# v2_0.net
KiCad netlist of a schematic drawn in Altium Designer
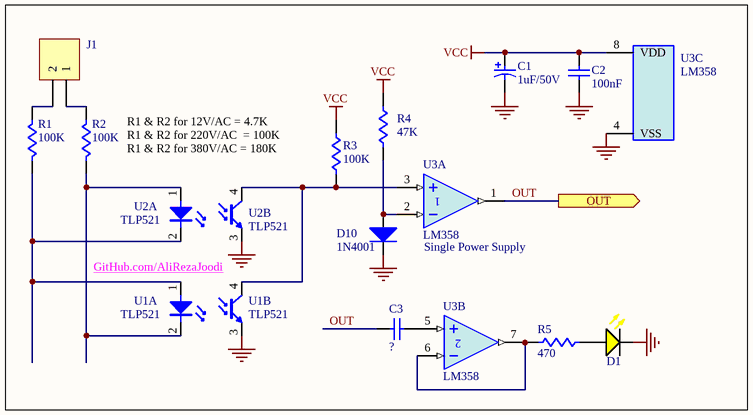
[diagram p0: v2.0.SchDoc]

(export (version "E")
  (design (tool "Eeschema 10.0.6"))
  (components
    (comp (ref "C1")
      (value "1uF/50V")
      (footprint "C_THD_EL_(P2.54-D6-H11)")
      (description "Capacitor, Electrolytic")
      (libsource (lib "Passive") (part "Capacitor_Electrolytic"))
    )
    (comp (ref "C2")
      (value "100nF")
      (footprint "C_THD_CER_(P2.54-D3.5-T1.5)")
      (description "Capacitor, Ceramic Multilayer")
      (libsource (lib "Passive") (part "Capacitor_Ceramic"))
    )
    (comp (ref "C3")
      (value "?")
      (footprint "C_THD_CER_(P2.54-D3.5-T1.5)")
      (description "Capacitor, Ceramic Multilayer")
      (libsource (lib "Passive") (part "Capacitor_Ceramic"))
    )
    (comp (ref "D1")
      (value "YELLOW")
      (footprint "LED_THD_5MM_YELLOW")
      (description "LED, Yellow")
      (fields (field (name "MANUFACTURER") "Generic Components") (field (name "PUBLISHER") "Altium Limited"))
      (libsource (lib "Display") (part "LED_YELLOW"))
    )
    (comp (ref "D10")
      (value "1N4001")
      (footprint "DIODE-0.4")
      (description "Default Diode")
      (fields (field (name "MANUFACTURER") "Generic Components") (field (name "PUBLISHER") "Altium Limited"))
      (libsource (lib "Miscellaneous Devices") (part "Diode"))
    )
    (comp (ref "J1")
      (value "Header 2")
      (footprint "Fonics_2PIN_1")
      (description "Header, 2-Pin")
      (fields (field (name "PUBLISHER") "Altium Limited"))
      (libsource (lib "Miscellaneous Connectors") (part "Header 2"))
    )
    (comp (ref "R1")
      (value "100K")
      (footprint "AXIAL-0.4")
      (description "Resistor")
      (fields
        (field (name "MANUFACTURER") "Generic Components")
        (field (name "Comment") "Res1")
        (field (name "PUBLISHER") "Altium Limited")
      )
      (libsource (lib "Miscellaneous Devices") (part "Res1"))
    )
    (comp (ref "R2")
      (value "100K")
      (footprint "AXIAL-0.4")
      (description "Resistor")
      (fields
        (field (name "MANUFACTURER") "Generic Components")
        (field (name "Comment") "Res1")
        (field (name "PUBLISHER") "Altium Limited")
      )
      (libsource (lib "Miscellaneous Devices") (part "Res1"))
    )
    (comp (ref "R3")
      (value "100K")
      (footprint "AXIAL-0.4")
      (description "Resistor")
      (fields
        (field (name "MANUFACTURER") "Generic Components")
        (field (name "Comment") "Res1")
        (field (name "PUBLISHER") "Altium Limited")
      )
      (libsource (lib "Miscellaneous Devices") (part "Res1"))
    )
    (comp (ref "R4")
      (value "47K")
      (footprint "AXIAL-0.4")
      (description "Resistor")
      (fields
        (field (name "MANUFACTURER") "Generic Components")
        (field (name "Comment") "Res1")
        (field (name "PUBLISHER") "Altium Limited")
      )
      (libsource (lib "Miscellaneous Devices") (part "Res1"))
    )
    (comp (ref "R5")
      (value "470")
      (footprint "AXIAL-0.4")
      (description "Resistor")
      (fields
        (field (name "MANUFACTURER") "Generic Components")
        (field (name "Comment") "Res1")
        (field (name "PUBLISHER") "Altium Limited")
      )
      (libsource (lib "Miscellaneous Devices") (part "Res1"))
    )
    (comp (ref "U1")
      (value "TLP521")
      (footprint "DIP-4")
      (fields (field (name "Comment") "Optoisolator") (field (name "PUBLISHER") "Altium Limited"))
      (libsource (lib "my Libraries") (part "Optoisolator"))
    )
    (comp (ref "U2")
      (value "TLP521")
      (footprint "DIP-4")
      (fields (field (name "Comment") "Optoisolator") (field (name "PUBLISHER") "Altium Limited"))
      (libsource (lib "my Libraries") (part "Optoisolator"))
    )
    (comp (ref "U3")
      (value "LM358")
      (footprint "DIP_8")
      (description "Dual Low-Power Operational Amplifier")
      (fields (field (name "PUBLISHER") "Altium Limited"))
      (libsource (lib "Op-Amp") (part "LM358"))
    )
  )
  (nets
    (net (code "1") (name "/OUT") (class "Default")
      (node (ref "C3") (pin "1") (pinfunction "1_1") (pintype "passive"))
      (node (ref "U3") (pin "1") (pinfunction "OUT_1") (pintype "output"))
    )
    (net (code "2") (name "GND") (class "Default")
      (node (ref "C1") (pin "2") (pinfunction "2_2") (pintype "passive"))
      (node (ref "C2") (pin "2") (pinfunction "2_2") (pintype "passive"))
      (node (ref "D1") (pin "2") (pinfunction "K_2") (pintype "passive"))
      (node (ref "D10") (pin "2") (pinfunction "K_2") (pintype "passive"))
      (node (ref "U1") (pin "3") (pinfunction "E_3") (pintype "passive"))
      (node (ref "U2") (pin "3") (pinfunction "E_3") (pintype "passive"))
      (node (ref "U3") (pin "4") (pinfunction "VSS_4") (pintype "power_in"))
    )
    (net (code "3") (name "Net-(D1-A)") (class "Default")
      (node (ref "D1") (pin "1") (pinfunction "A_1") (pintype "passive"))
      (node (ref "R5") (pin "2") (pinfunction "2_2") (pintype "passive"))
    )
    (net (code "4") (name "Net-(D10-A)") (class "Default")
      (node (ref "D10") (pin "1") (pinfunction "A_1") (pintype "passive"))
      (node (ref "R4") (pin "2") (pinfunction "2_2") (pintype "passive"))
      (node (ref "U3") (pin "2") (pinfunction "IN-_2") (pintype "input"))
    )
    (net (code "5") (name "Net-(J1-Pad1)") (class "Default")
      (node (ref "J1") (pin "1") (pinfunction "1_1") (pintype "passive"))
      (node (ref "R2") (pin "1") (pinfunction "1_1") (pintype "passive"))
    )
    (net (code "6") (name "Net-(J1-Pad2)") (class "Default")
      (node (ref "J1") (pin "2") (pinfunction "2_2") (pintype "passive"))
      (node (ref "R1") (pin "1") (pinfunction "1_1") (pintype "passive"))
    )
    (net (code "7") (name "Net-(U1A-A)") (class "Default")
      (node (ref "R1") (pin "2") (pinfunction "2_2") (pintype "passive"))
      (node (ref "U1") (pin "1") (pinfunction "A_1") (pintype "power_in"))
      (node (ref "U2") (pin "2") (pinfunction "K_2") (pintype "power_in"))
    )
    (net (code "8") (name "Net-(U1A-K)") (class "Default")
      (node (ref "R2") (pin "2") (pinfunction "2_2") (pintype "passive"))
      (node (ref "U1") (pin "2") (pinfunction "K_2") (pintype "power_in"))
      (node (ref "U2") (pin "1") (pinfunction "A_1") (pintype "power_in"))
    )
    (net (code "9") (name "Net-(U1B-C)") (class "Default")
      (node (ref "R3") (pin "2") (pinfunction "2_2") (pintype "passive"))
      (node (ref "U1") (pin "4") (pinfunction "C_4") (pintype "passive"))
      (node (ref "U2") (pin "4") (pinfunction "C_4") (pintype "passive"))
      (node (ref "U3") (pin "3") (pinfunction "IN+_3") (pintype "input"))
    )
    (net (code "10") (name "Net-(U3B-IN+)") (class "Default")
      (node (ref "C3") (pin "2") (pinfunction "2_2") (pintype "passive"))
      (node (ref "U3") (pin "5") (pinfunction "IN+_5") (pintype "input"))
    )
    (net (code "11") (name "Net-(U3B-IN-)") (class "Default")
      (node (ref "R5") (pin "1") (pinfunction "1_1") (pintype "passive"))
      (node (ref "U3") (pin "6") (pinfunction "IN-_6") (pintype "input"))
      (node (ref "U3") (pin "7") (pinfunction "OUT_7") (pintype "output"))
    )
    (net (code "12") (name "VCC") (class "Default")
      (node (ref "C1") (pin "1") (pinfunction "1_1") (pintype "passive"))
      (node (ref "C2") (pin "1") (pinfunction "1_1") (pintype "passive"))
      (node (ref "R3") (pin "1") (pinfunction "1_1") (pintype "passive"))
      (node (ref "R4") (pin "1") (pinfunction "1_1") (pintype "passive"))
      (node (ref "U3") (pin "8") (pinfunction "VDD_8") (pintype "passive"))
    )
  )
)
